# untitled.net
KiCad netlist of a schematic drawn in EAGLE
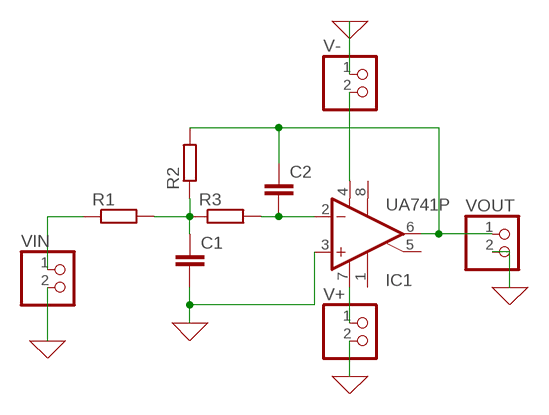
[diagram p0: schematic, sheet 1]

(export (version "E")
  (design (tool "Eeschema 10.0.6"))
  (components
    (comp (ref "C1")
      (value "C-EU025-025X050")
      (footprint "eagle-import:C025-025X050")
      (libsource (lib "eagle-import") (part "C-EU025-025X050"))
    )
    (comp (ref "C2")
      (value "C-EU025-025X050")
      (footprint "eagle-import:C025-025X050")
      (libsource (lib "eagle-import") (part "C-EU025-025X050"))
    )
    (comp (ref "IC1")
      (value "UA741P")
      (footprint "eagle-import:DIL08")
      (libsource (lib "eagle-import") (part "741PUA"))
    )
    (comp (ref "R1")
      (value "R-EU_0411/3V")
      (footprint "eagle-import:0411V")
      (libsource (lib "eagle-import") (part "R-EU_0411/3V"))
    )
    (comp (ref "R2")
      (value "R-EU_0411/3V")
      (footprint "eagle-import:0411V")
      (libsource (lib "eagle-import") (part "R-EU_0411/3V"))
    )
    (comp (ref "R3")
      (value "R-EU_0411/3V")
      (footprint "eagle-import:0411V")
      (libsource (lib "eagle-import") (part "R-EU_0411/3V"))
    )
    (comp (ref "V+")
      (value "PINHD-1X2")
      (footprint "eagle-import:1X02")
      (libsource (lib "eagle-import") (part "PINHD-1X2"))
    )
    (comp (ref "V-")
      (value "PINHD-1X2")
      (footprint "eagle-import:1X02")
      (libsource (lib "eagle-import") (part "PINHD-1X2"))
    )
    (comp (ref "VIN")
      (value "PINHD-1X2")
      (footprint "eagle-import:1X02")
      (libsource (lib "eagle-import") (part "PINHD-1X2"))
    )
    (comp (ref "VOUT")
      (value "PINHD-1X2")
      (footprint "eagle-import:1X02")
      (libsource (lib "eagle-import") (part "PINHD-1X2"))
    )
  )
  (nets
    (net (code "1") (name "GND") (class "Default")
      (node (ref "C1") (pin "2") (pinfunction "2_2") (pintype "passive"))
      (node (ref "IC1") (pin "3") (pinfunction "+IN_3") (pintype "input"))
      (node (ref "V+") (pin "2") (pinfunction "2_2") (pintype "passive"))
      (node (ref "V-") (pin "1") (pinfunction "1_1") (pintype "passive"))
      (node (ref "VIN") (pin "2") (pinfunction "2_2") (pintype "passive"))
      (node (ref "VOUT") (pin "2") (pinfunction "2_2") (pintype "passive"))
    )
    (net (code "2") (name "Net-(C1-Pad1)") (class "Default")
      (node (ref "C1") (pin "1") (pinfunction "1_1") (pintype "passive"))
      (node (ref "R1") (pin "2") (pinfunction "2_2") (pintype "passive"))
      (node (ref "R2") (pin "1") (pinfunction "1_1") (pintype "passive"))
      (node (ref "R3") (pin "1") (pinfunction "1_1") (pintype "passive"))
    )
    (net (code "3") (name "Net-(IC1--IN)") (class "Default")
      (node (ref "C2") (pin "2") (pinfunction "2_2") (pintype "passive"))
      (node (ref "IC1") (pin "2") (pinfunction "-IN_2") (pintype "input"))
      (node (ref "R3") (pin "2") (pinfunction "2_2") (pintype "passive"))
    )
    (net (code "4") (name "Net-(IC1-OUT)") (class "Default")
      (node (ref "C2") (pin "1") (pinfunction "1_1") (pintype "passive"))
      (node (ref "IC1") (pin "6") (pinfunction "OUT_6") (pintype "output"))
      (node (ref "R2") (pin "2") (pinfunction "2_2") (pintype "passive"))
      (node (ref "VOUT") (pin "1") (pinfunction "1_1") (pintype "passive"))
    )
    (net (code "5") (name "Net-(IC1-V+)") (class "Default")
      (node (ref "IC1") (pin "7") (pinfunction "V+_7") (pintype "power_in"))
      (node (ref "V+") (pin "1") (pinfunction "1_1") (pintype "passive"))
    )
    (net (code "6") (name "Net-(IC1-V-)") (class "Default")
      (node (ref "IC1") (pin "4") (pinfunction "V-_4") (pintype "power_in"))
      (node (ref "V-") (pin "2") (pinfunction "2_2") (pintype "passive"))
    )
    (net (code "7") (name "Net-(R1-Pad1)") (class "Default")
      (node (ref "R1") (pin "1") (pinfunction "1_1") (pintype "passive"))
      (node (ref "VIN") (pin "1") (pinfunction "1_1") (pintype "passive"))
    )
    (net (code "8") (name "unconnected-(IC1-ON1-Pad1)") (class "Default")
      (node (ref "IC1") (pin "1") (pinfunction "ON1_1") (pintype "passive"))
    )
    (net (code "9") (name "unconnected-(IC1-ON2-Pad5)") (class "Default")
      (node (ref "IC1") (pin "5") (pinfunction "ON2_5") (pintype "passive"))
    )
    (net (code "10") (name "unconnected-(IC1-OPT-Pad8)") (class "Default")
      (node (ref "IC1") (pin "8") (pinfunction "OPT_8") (pintype "passive"))
    )
  )
)
